# Sheet1.net
KiCad netlist of a schematic drawn in Altium Designer
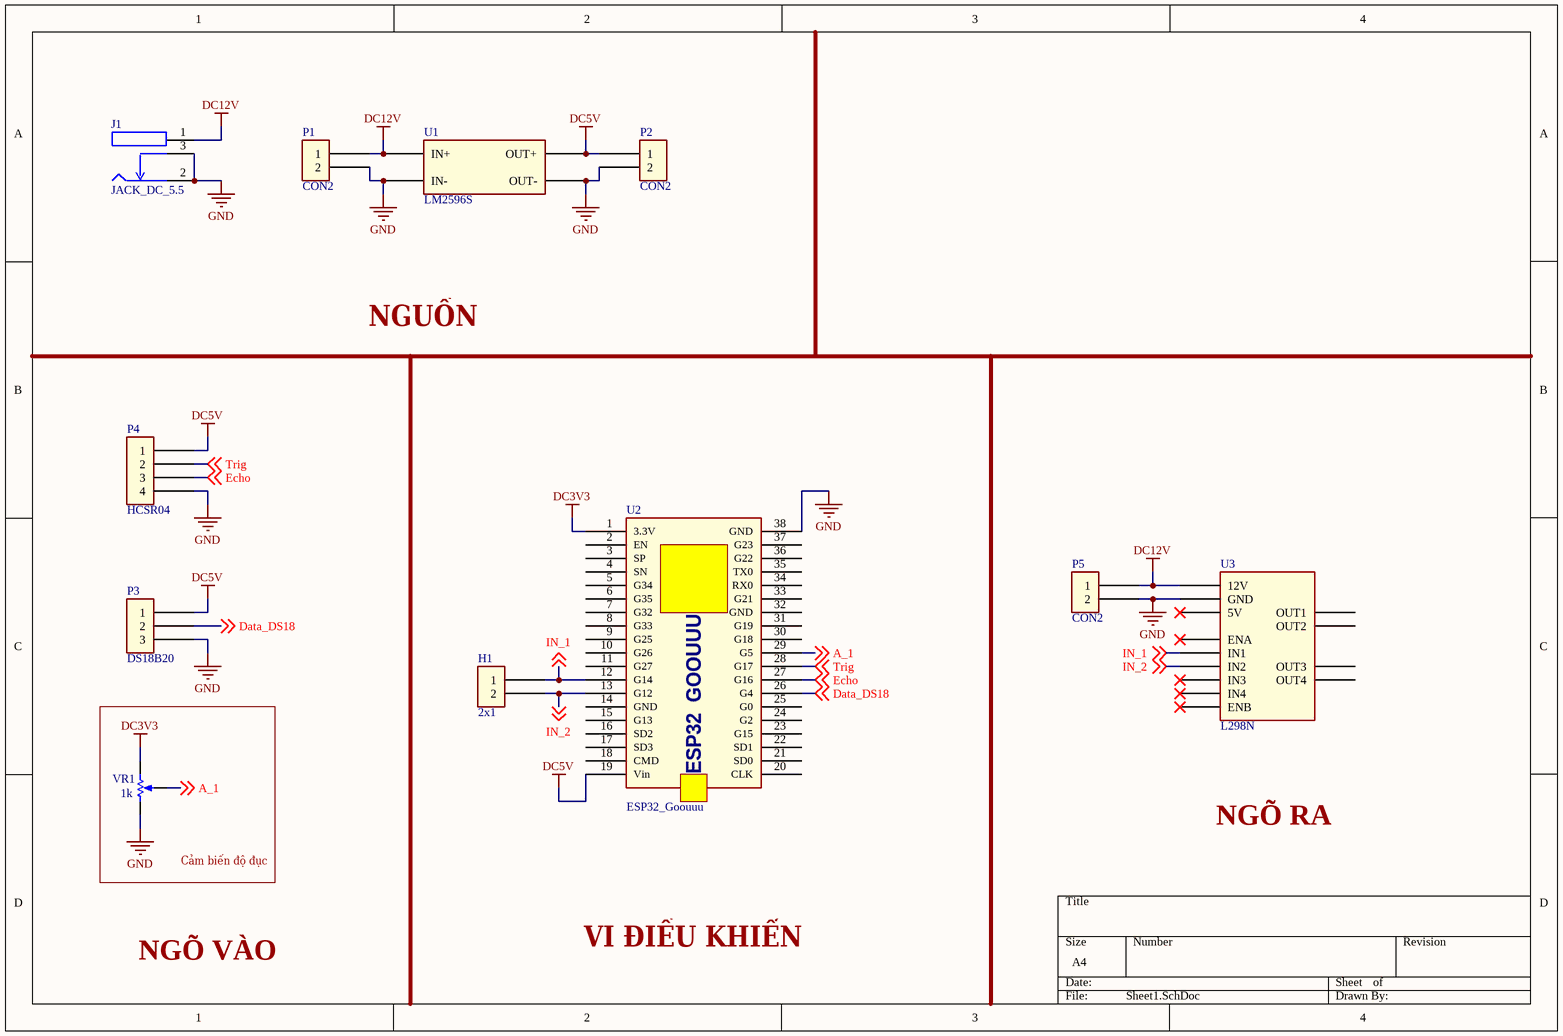
[diagram p0: Sheet1.SchDoc]

(export (version "E")
  (design (tool "Eeschema 10.0.6"))
  (components
    (comp (ref "H1")
      (value "2x1")
      (footprint "HED_2X1_1")
      (description "Header 2x1")
      (libsource (lib "SachTran_Lib") (part "HEADER_2X1"))
    )
    (comp (ref "J1")
      (value "JACK_DC_5.5")
      (footprint "DC5.5/2.1")
      (description "Jack DC 5.5x2.1")
      (libsource (lib "SachTran_Lib") (part "JACK_DC_5.5"))
    )
    (comp (ref "P1")
      (value "CON2")
      (footprint "CON2")
      (description "Connector 2")
      (libsource (lib "") (part "CON2_1"))
    )
    (comp (ref "P2")
      (value "CON2")
      (footprint "CON2")
      (description "Connector 2")
      (libsource (lib "SachTran_Lib") (part "CON2"))
    )
    (comp (ref "P3")
      (value "DS18B20")
      (footprint "CON3")
      (description "Connector 3")
      (libsource (lib "SachTran_Lib") (part "CON3"))
    )
    (comp (ref "P4")
      (value "HCSR04")
      (footprint "CON4")
      (description "Connector 4")
      (libsource (lib "SachTran_Lib") (part "CON4"))
    )
    (comp (ref "P5")
      (value "CON2")
      (footprint "CON2")
      (description "Connector 2")
      (libsource (lib "") (part "CON2_1"))
    )
    (comp (ref "U1")
      (value "LM2596S")
      (footprint "LM2596S")
      (libsource (lib "SachTran_Lib") (part "LM2596S"))
    )
    (comp (ref "U2")
      (value "ESP32_Goouuu")
      (footprint "ESP32_Goouuu")
      (libsource (lib "SachTran_Lib") (part "ESP32_Goouuu"))
    )
    (comp (ref "U3") (value "L298N") (footprint "L298N") (libsource (lib "SachTran_Lib") (part "L298N")))
    (comp (ref "VR1")
      (value "1k")
      (footprint "VR_VOLUME")
      (description "Variable_Resistor Volume 1K")
      (libsource (lib "SachTran_Lib") (part "VR_Volume 1K"))
    )
  )
  (nets
    (net (code "1") (name "A_1") (class "Default")
      (node (ref "U2") (pin "29") (pinfunction "G5_29") (pintype "passive"))
      (node (ref "VR1") (pin "2") (pinfunction "WIPER_2") (pintype "passive"))
    )
    (net (code "2") (name "DC3V3") (class "Default")
      (node (ref "U2") (pin "1") (pinfunction "3.3V_1") (pintype "passive"))
      (node (ref "VR1") (pin "1") (pinfunction "CCW_1") (pintype "passive"))
    )
    (net (code "3") (name "DC5V") (class "Default")
      (node (ref "P2") (pin "1") (pinfunction "1_1") (pintype "passive"))
      (node (ref "P3") (pin "1") (pinfunction "1_1") (pintype "passive"))
      (node (ref "P4") (pin "1") (pinfunction "1_1") (pintype "passive"))
      (node (ref "U1") (pin "1") (pinfunction "OUT+_1") (pintype "open_emitter"))
      (node (ref "U2") (pin "19") (pinfunction "Vin_19") (pintype "passive"))
    )
    (net (code "4") (name "DC12V") (class "Default")
      (node (ref "J1") (pin "1") (pinfunction "1_1") (pintype "passive"))
      (node (ref "P1") (pin "1") (pinfunction "1_1") (pintype "passive"))
      (node (ref "P5") (pin "1") (pinfunction "1_1") (pintype "passive"))
      (node (ref "U1") (pin "1") (pinfunction "IN+_1") (pintype "open_emitter"))
      (node (ref "U3") (pin "1") (pinfunction "12V_1") (pintype "passive"))
    )
    (net (code "5") (name "Data_DS18") (class "Default")
      (node (ref "P3") (pin "2") (pinfunction "2_2") (pintype "passive"))
      (node (ref "U2") (pin "26") (pinfunction "G4_26") (pintype "passive"))
    )
    (net (code "6") (name "Echo") (class "Default")
      (node (ref "P4") (pin "3") (pinfunction "3_3") (pintype "passive"))
      (node (ref "U2") (pin "27") (pinfunction "G16_27") (pintype "passive"))
    )
    (net (code "7") (name "GND") (class "Default")
      (node (ref "J1") (pin "2") (pinfunction "2_2") (pintype "passive"))
      (node (ref "J1") (pin "3") (pinfunction "3_3") (pintype "passive"))
      (node (ref "P1") (pin "2") (pinfunction "2_2") (pintype "passive"))
      (node (ref "P2") (pin "2") (pinfunction "2_2") (pintype "passive"))
      (node (ref "P3") (pin "3") (pinfunction "3_3") (pintype "passive"))
      (node (ref "P4") (pin "4") (pinfunction "4_4") (pintype "passive"))
      (node (ref "P5") (pin "2") (pinfunction "2_2") (pintype "passive"))
      (node (ref "U1") (pin "1") (pinfunction "IN-_1") (pintype "open_emitter"))
      (node (ref "U2") (pin "38") (pinfunction "GND_38") (pintype "passive"))
      (node (ref "U3") (pin "1") (pinfunction "GND_1") (pintype "passive"))
      (node (ref "VR1") (pin "3") (pinfunction "CW_3") (pintype "passive"))
    )
    (net (code "8") (name "IN_1") (class "Default")
      (node (ref "H1") (pin "1") (pinfunction "1_1") (pintype "passive"))
      (node (ref "U2") (pin "12") (pinfunction "G14_12") (pintype "passive"))
      (node (ref "U3") (pin "1") (pinfunction "IN1_1") (pintype "passive"))
    )
    (net (code "9") (name "IN_2") (class "Default")
      (node (ref "H1") (pin "2") (pinfunction "2_2") (pintype "passive"))
      (node (ref "U2") (pin "13") (pinfunction "G12_13") (pintype "passive"))
      (node (ref "U3") (pin "1") (pinfunction "IN2_1") (pintype "passive"))
    )
    (net (code "10") (name "Trig") (class "Default")
      (node (ref "P4") (pin "2") (pinfunction "2_2") (pintype "passive"))
      (node (ref "U2") (pin "28") (pinfunction "G17_28") (pintype "passive"))
    )
    (net (code "11") (name "unconnected-(U2-CLK-Pad20)") (class "Default")
      (node (ref "U2") (pin "20") (pinfunction "CLK_20") (pintype "passive"))
    )
    (net (code "12") (name "unconnected-(U2-CMD-Pad18)") (class "Default")
      (node (ref "U2") (pin "18") (pinfunction "CMD_18") (pintype "passive"))
    )
    (net (code "13") (name "unconnected-(U2-EN-Pad2)") (class "Default")
      (node (ref "U2") (pin "2") (pinfunction "EN_2") (pintype "passive"))
    )
    (net (code "14") (name "unconnected-(U2-G0-Pad25)") (class "Default")
      (node (ref "U2") (pin "25") (pinfunction "G0_25") (pintype "passive"))
    )
    (net (code "15") (name "unconnected-(U2-G2-Pad24)") (class "Default")
      (node (ref "U2") (pin "24") (pinfunction "G2_24") (pintype "passive"))
    )
    (net (code "16") (name "unconnected-(U2-G13-Pad15)") (class "Default")
      (node (ref "U2") (pin "15") (pinfunction "G13_15") (pintype "passive"))
    )
    (net (code "17") (name "unconnected-(U2-G15-Pad23)") (class "Default")
      (node (ref "U2") (pin "23") (pinfunction "G15_23") (pintype "passive"))
    )
    (net (code "18") (name "unconnected-(U2-G18-Pad30)") (class "Default")
      (node (ref "U2") (pin "30") (pinfunction "G18_30") (pintype "passive"))
    )
    (net (code "19") (name "unconnected-(U2-G19-Pad31)") (class "Default")
      (node (ref "U2") (pin "31") (pinfunction "G19_31") (pintype "passive"))
    )
    (net (code "20") (name "unconnected-(U2-G21-Pad33)") (class "Default")
      (node (ref "U2") (pin "33") (pinfunction "G21_33") (pintype "passive"))
    )
    (net (code "21") (name "unconnected-(U2-G22-Pad36)") (class "Default")
      (node (ref "U2") (pin "36") (pinfunction "G22_36") (pintype "passive"))
    )
    (net (code "22") (name "unconnected-(U2-G23-Pad37)") (class "Default")
      (node (ref "U2") (pin "37") (pinfunction "G23_37") (pintype "passive"))
    )
    (net (code "23") (name "unconnected-(U2-G25-Pad9)") (class "Default")
      (node (ref "U2") (pin "9") (pinfunction "G25_9") (pintype "passive"))
    )
    (net (code "24") (name "unconnected-(U2-G26-Pad10)") (class "Default")
      (node (ref "U2") (pin "10") (pinfunction "G26_10") (pintype "passive"))
    )
    (net (code "25") (name "unconnected-(U2-G27-Pad11)") (class "Default")
      (node (ref "U2") (pin "11") (pinfunction "G27_11") (pintype "passive"))
    )
    (net (code "26") (name "unconnected-(U2-G32-Pad7)") (class "Default")
      (node (ref "U2") (pin "7") (pinfunction "G32_7") (pintype "passive"))
    )
    (net (code "27") (name "unconnected-(U2-G33-Pad8)") (class "Default")
      (node (ref "U2") (pin "8") (pinfunction "G33_8") (pintype "passive"))
    )
    (net (code "28") (name "unconnected-(U2-G34-Pad5)") (class "Default")
      (node (ref "U2") (pin "5") (pinfunction "G34_5") (pintype "passive"))
    )
    (net (code "29") (name "unconnected-(U2-G35-Pad6)") (class "Default")
      (node (ref "U2") (pin "6") (pinfunction "G35_6") (pintype "passive"))
    )
    (net (code "30") (name "unconnected-(U2-GND-Pad14)") (class "Default")
      (node (ref "U2") (pin "14") (pinfunction "GND_14") (pintype "passive"))
    )
    (net (code "31") (name "unconnected-(U2-GND-Pad32)") (class "Default")
      (node (ref "U2") (pin "32") (pinfunction "GND_32") (pintype "passive"))
    )
    (net (code "32") (name "unconnected-(U2-RX0-Pad34)") (class "Default")
      (node (ref "U2") (pin "34") (pinfunction "RX0_34") (pintype "passive"))
    )
    (net (code "33") (name "unconnected-(U2-SD0-Pad21)") (class "Default")
      (node (ref "U2") (pin "21") (pinfunction "SD0_21") (pintype "passive"))
    )
    (net (code "34") (name "unconnected-(U2-SD1-Pad22)") (class "Default")
      (node (ref "U2") (pin "22") (pinfunction "SD1_22") (pintype "passive"))
    )
    (net (code "35") (name "unconnected-(U2-SD2-Pad16)") (class "Default")
      (node (ref "U2") (pin "16") (pinfunction "SD2_16") (pintype "passive"))
    )
    (net (code "36") (name "unconnected-(U2-SD3-Pad17)") (class "Default")
      (node (ref "U2") (pin "17") (pinfunction "SD3_17") (pintype "passive"))
    )
    (net (code "37") (name "unconnected-(U2-SN-Pad4)") (class "Default")
      (node (ref "U2") (pin "4") (pinfunction "SN_4") (pintype "passive"))
    )
    (net (code "38") (name "unconnected-(U2-SP-Pad3)") (class "Default")
      (node (ref "U2") (pin "3") (pinfunction "SP_3") (pintype "passive"))
    )
    (net (code "39") (name "unconnected-(U2-TX0-Pad35)") (class "Default")
      (node (ref "U2") (pin "35") (pinfunction "TX0_35") (pintype "passive"))
    )
    (net (code "40") (name "unconnected-(U3-5V-Pad1)") (class "Default")
      (node (ref "U3") (pin "1") (pinfunction "5V_1") (pintype "passive+no_connect"))
    )
    (net (code "41") (name "unconnected-(U3-ENA-Pad1)") (class "Default")
      (node (ref "U3") (pin "1") (pinfunction "ENA_1") (pintype "passive+no_connect"))
    )
    (net (code "42") (name "unconnected-(U3-ENB-Pad1)") (class "Default")
      (node (ref "U3") (pin "1") (pinfunction "ENB_1") (pintype "passive+no_connect"))
    )
    (net (code "43") (name "unconnected-(U3-IN3-Pad1)") (class "Default")
      (node (ref "U3") (pin "1") (pinfunction "IN3_1") (pintype "passive+no_connect"))
    )
    (net (code "44") (name "unconnected-(U3-IN4-Pad1)") (class "Default")
      (node (ref "U3") (pin "1") (pinfunction "IN4_1") (pintype "passive+no_connect"))
    )
    (net (code "45") (name "unconnected-(U3-OUT1-Pad1)") (class "Default")
      (node (ref "U3") (pin "1") (pinfunction "OUT1_1") (pintype "passive"))
    )
    (net (code "46") (name "unconnected-(U3-OUT2-Pad1)") (class "Default")
      (node (ref "U3") (pin "1") (pinfunction "OUT2_1") (pintype "passive"))
    )
    (net (code "47") (name "unconnected-(U3-OUT3-Pad1)") (class "Default")
      (node (ref "U3") (pin "1") (pinfunction "OUT3_1") (pintype "passive"))
    )
    (net (code "48") (name "unconnected-(U3-OUT4-Pad1)") (class "Default")
      (node (ref "U3") (pin "1") (pinfunction "OUT4_1") (pintype "passive"))
    )
  )
)
